# driver_1.net
KiCad netlist of a schematic drawn in EAGLE
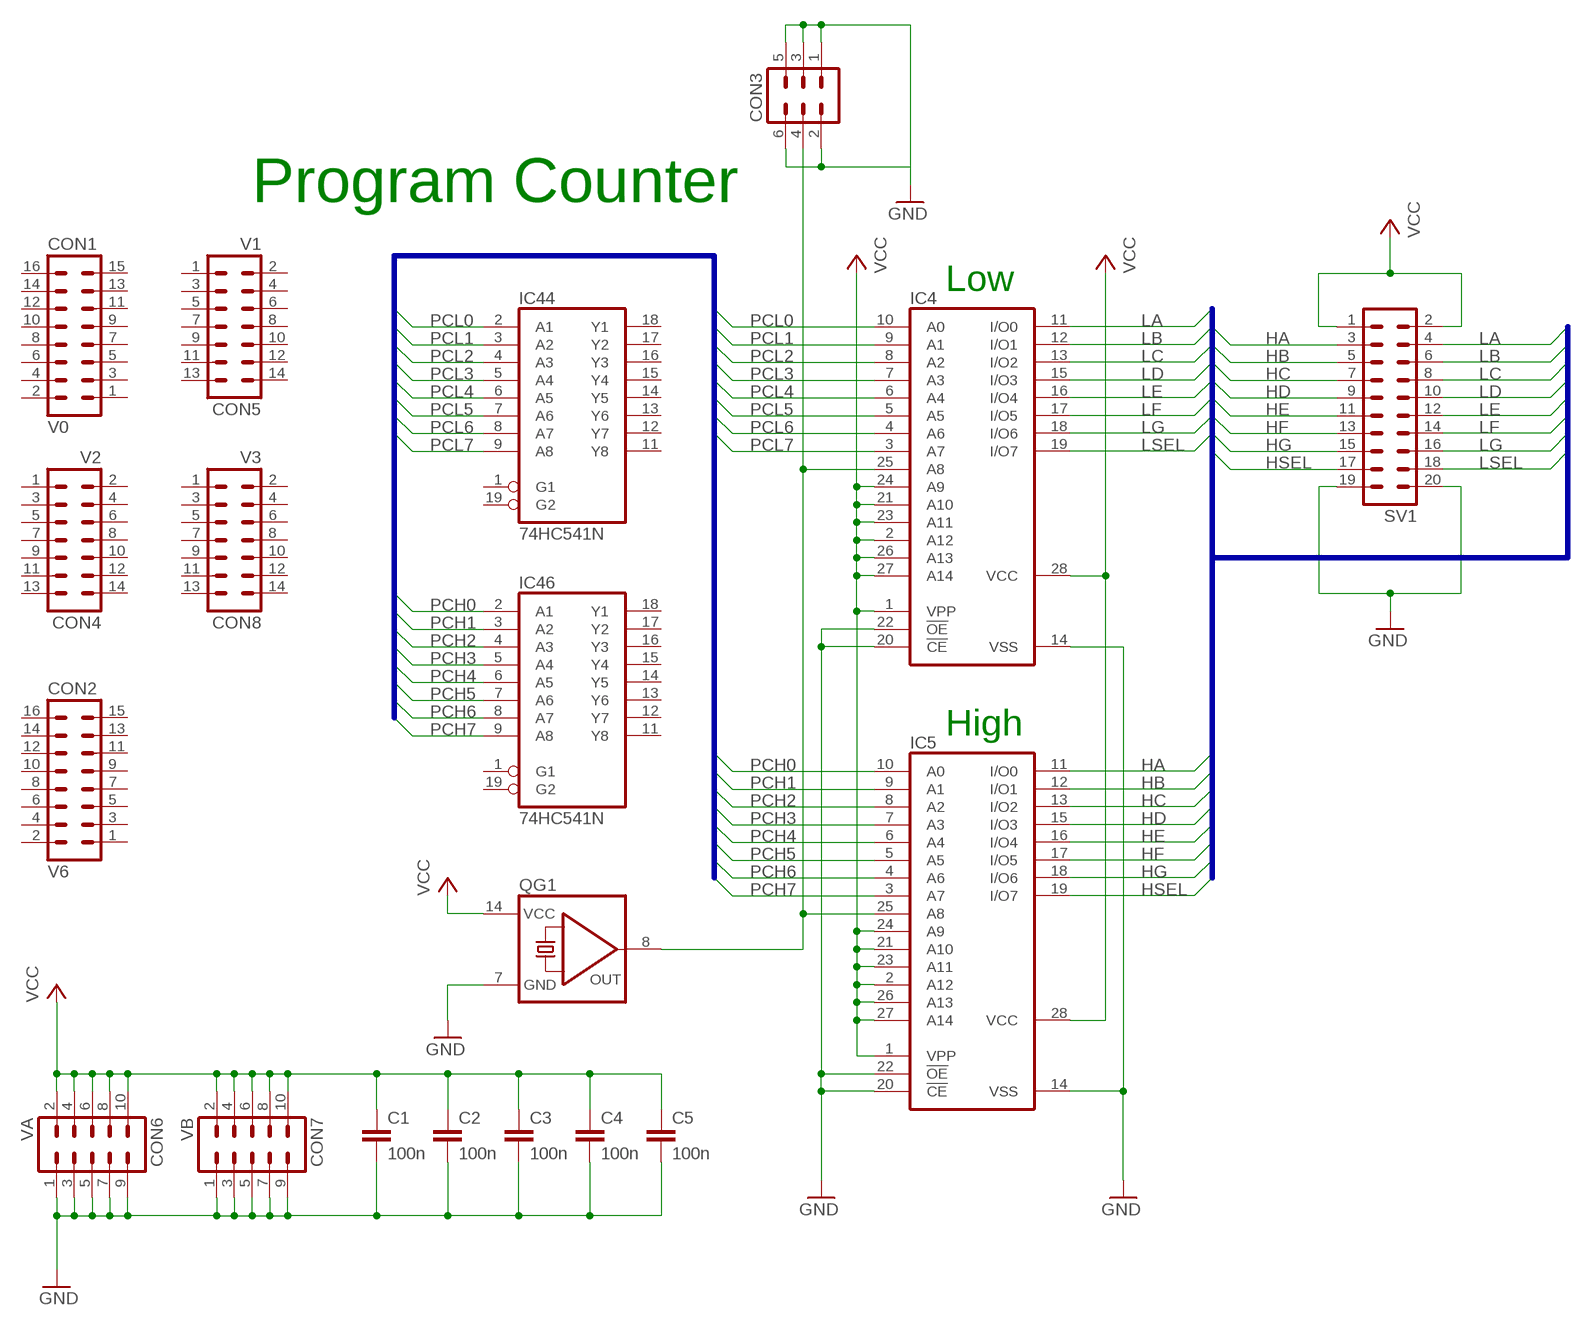
[diagram p0: schematic, sheet 1]

(export (version "E")
  (design (tool "Eeschema 10.0.6"))
  (components
    (comp (ref "C1")
      (value "100n")
      (footprint "eagle-import:C050-024X044")
      (libsource (lib "eagle-import") (part "C-EU050-024X044"))
    )
    (comp (ref "C2")
      (value "100n")
      (footprint "eagle-import:C050-024X044")
      (libsource (lib "eagle-import") (part "C-EU050-024X044"))
    )
    (comp (ref "C3")
      (value "100n")
      (footprint "eagle-import:C050-024X044")
      (libsource (lib "eagle-import") (part "C-EU050-024X044"))
    )
    (comp (ref "C4")
      (value "100n")
      (footprint "eagle-import:C050-024X044")
      (libsource (lib "eagle-import") (part "C-EU050-024X044"))
    )
    (comp (ref "C5")
      (value "100n")
      (footprint "eagle-import:C050-024X044")
      (libsource (lib "eagle-import") (part "C-EU050-024X044"))
    )
    (comp (ref "CON1")
      (value "V0")
      (footprint "eagle-import:ML16")
      (libsource (lib "eagle-import") (part "ML16"))
    )
    (comp (ref "CON2")
      (value "V6")
      (footprint "eagle-import:ML16")
      (libsource (lib "eagle-import") (part "ML16"))
    )
    (comp (ref "CON3")
      (value "ML6")
      (footprint "eagle-import:ML6")
      (libsource (lib "eagle-import") (part "ML6"))
    )
    (comp (ref "CON4")
      (value "V2")
      (footprint "eagle-import:ML14")
      (libsource (lib "eagle-import") (part "ML14"))
    )
    (comp (ref "CON5")
      (value "V1")
      (footprint "eagle-import:ML14")
      (fields (field (name "OC_FARNELL") "unknown") (field (name "OC_NEWARK") "unknown"))
      (libsource (lib "eagle-import") (part "ML14"))
    )
    (comp (ref "CON6")
      (value "VA")
      (footprint "eagle-import:ML10")
      (libsource (lib "eagle-import") (part "ML10"))
    )
    (comp (ref "CON7")
      (value "VB")
      (footprint "eagle-import:ML10")
      (libsource (lib "eagle-import") (part "ML10"))
    )
    (comp (ref "CON8")
      (value "V3")
      (footprint "eagle-import:ML14")
      (libsource (lib "eagle-import") (part "ML14"))
    )
    (comp (ref "IC4")
      (value "27C256AG")
      (footprint "eagle-import:DIL28-6")
      (libsource (lib "eagle-import") (part "27C256AG"))
    )
    (comp (ref "IC5")
      (value "27C256AG")
      (footprint "eagle-import:DIL28-6")
      (libsource (lib "eagle-import") (part "27C256AG"))
    )
    (comp (ref "IC44")
      (value "74HC541N")
      (footprint "eagle-import:DIL20")
      (libsource (lib "eagle-import") (part "74541NHC"))
    )
    (comp (ref "IC46")
      (value "74HC541N")
      (footprint "eagle-import:DIL20")
      (libsource (lib "eagle-import") (part "74541NHC"))
    )
    (comp (ref "QG1")
      (value "QG5860")
      (footprint "eagle-import:DIL14S")
      (libsource (lib "eagle-import") (part "QG5860"))
    )
    (comp (ref "SV1")
      (value "ML20L")
      (footprint "eagle-import:ML20L")
      (libsource (lib "eagle-import") (part "ML20L"))
    )
  )
  (nets
    (net (code "1") (name "/HA") (class "Default")
      (node (ref "IC5") (pin "11") (pinfunction "I/O0_11") (pintype "tri_state"))
      (node (ref "SV1") (pin "3") (pinfunction "3_3") (pintype "passive"))
    )
    (net (code "2") (name "/HB") (class "Default")
      (node (ref "IC5") (pin "12") (pinfunction "I/O1_12") (pintype "tri_state"))
      (node (ref "SV1") (pin "5") (pinfunction "5_5") (pintype "passive"))
    )
    (net (code "3") (name "/HC") (class "Default")
      (node (ref "IC5") (pin "13") (pinfunction "I/O2_13") (pintype "tri_state"))
      (node (ref "SV1") (pin "7") (pinfunction "7_7") (pintype "passive"))
    )
    (net (code "4") (name "/HD") (class "Default")
      (node (ref "IC5") (pin "15") (pinfunction "I/O3_15") (pintype "tri_state"))
      (node (ref "SV1") (pin "9") (pinfunction "9_9") (pintype "passive"))
    )
    (net (code "5") (name "/HE") (class "Default")
      (node (ref "IC5") (pin "16") (pinfunction "I/O4_16") (pintype "tri_state"))
      (node (ref "SV1") (pin "11") (pinfunction "11_11") (pintype "passive"))
    )
    (net (code "6") (name "/HF") (class "Default")
      (node (ref "IC5") (pin "17") (pinfunction "I/O5_17") (pintype "tri_state"))
      (node (ref "SV1") (pin "13") (pinfunction "13_13") (pintype "passive"))
    )
    (net (code "7") (name "/HG") (class "Default")
      (node (ref "IC5") (pin "18") (pinfunction "I/O6_18") (pintype "tri_state"))
      (node (ref "SV1") (pin "15") (pinfunction "15_15") (pintype "passive"))
    )
    (net (code "8") (name "/HSEL") (class "Default")
      (node (ref "IC5") (pin "19") (pinfunction "I/O7_19") (pintype "tri_state"))
      (node (ref "SV1") (pin "17") (pinfunction "17_17") (pintype "passive"))
    )
    (net (code "9") (name "/LA") (class "Default")
      (node (ref "IC4") (pin "11") (pinfunction "I/O0_11") (pintype "tri_state"))
      (node (ref "SV1") (pin "4") (pinfunction "4_4") (pintype "passive"))
    )
    (net (code "10") (name "/LB") (class "Default")
      (node (ref "IC4") (pin "12") (pinfunction "I/O1_12") (pintype "tri_state"))
      (node (ref "SV1") (pin "6") (pinfunction "6_6") (pintype "passive"))
    )
    (net (code "11") (name "/LC") (class "Default")
      (node (ref "IC4") (pin "13") (pinfunction "I/O2_13") (pintype "tri_state"))
      (node (ref "SV1") (pin "8") (pinfunction "8_8") (pintype "passive"))
    )
    (net (code "12") (name "/LD") (class "Default")
      (node (ref "IC4") (pin "15") (pinfunction "I/O3_15") (pintype "tri_state"))
      (node (ref "SV1") (pin "10") (pinfunction "10_10") (pintype "passive"))
    )
    (net (code "13") (name "/LE") (class "Default")
      (node (ref "IC4") (pin "16") (pinfunction "I/O4_16") (pintype "tri_state"))
      (node (ref "SV1") (pin "12") (pinfunction "12_12") (pintype "passive"))
    )
    (net (code "14") (name "/LF") (class "Default")
      (node (ref "IC4") (pin "17") (pinfunction "I/O5_17") (pintype "tri_state"))
      (node (ref "SV1") (pin "14") (pinfunction "14_14") (pintype "passive"))
    )
    (net (code "15") (name "/LG") (class "Default")
      (node (ref "IC4") (pin "18") (pinfunction "I/O6_18") (pintype "tri_state"))
      (node (ref "SV1") (pin "16") (pinfunction "16_16") (pintype "passive"))
    )
    (net (code "16") (name "/LSEL") (class "Default")
      (node (ref "IC4") (pin "19") (pinfunction "I/O7_19") (pintype "tri_state"))
      (node (ref "SV1") (pin "18") (pinfunction "18_18") (pintype "passive"))
    )
    (net (code "17") (name "/PCH0") (class "Default")
      (node (ref "IC46") (pin "2") (pinfunction "A1_2") (pintype "input"))
      (node (ref "IC5") (pin "10") (pinfunction "A0_10") (pintype "input"))
    )
    (net (code "18") (name "/PCH1") (class "Default")
      (node (ref "IC46") (pin "3") (pinfunction "A2_3") (pintype "input"))
      (node (ref "IC5") (pin "9") (pinfunction "A1_9") (pintype "input"))
    )
    (net (code "19") (name "/PCH2") (class "Default")
      (node (ref "IC46") (pin "4") (pinfunction "A3_4") (pintype "input"))
      (node (ref "IC5") (pin "8") (pinfunction "A2_8") (pintype "input"))
    )
    (net (code "20") (name "/PCH3") (class "Default")
      (node (ref "IC46") (pin "5") (pinfunction "A4_5") (pintype "input"))
      (node (ref "IC5") (pin "7") (pinfunction "A3_7") (pintype "input"))
    )
    (net (code "21") (name "/PCH4") (class "Default")
      (node (ref "IC46") (pin "6") (pinfunction "A5_6") (pintype "input"))
      (node (ref "IC5") (pin "6") (pinfunction "A4_6") (pintype "input"))
    )
    (net (code "22") (name "/PCH5") (class "Default")
      (node (ref "IC46") (pin "7") (pinfunction "A6_7") (pintype "input"))
      (node (ref "IC5") (pin "5") (pinfunction "A5_5") (pintype "input"))
    )
    (net (code "23") (name "/PCH6") (class "Default")
      (node (ref "IC46") (pin "8") (pinfunction "A7_8") (pintype "input"))
      (node (ref "IC5") (pin "4") (pinfunction "A6_4") (pintype "input"))
    )
    (net (code "24") (name "/PCH7") (class "Default")
      (node (ref "IC46") (pin "9") (pinfunction "A8_9") (pintype "input"))
      (node (ref "IC5") (pin "3") (pinfunction "A7_3") (pintype "input"))
    )
    (net (code "25") (name "/PCL0") (class "Default")
      (node (ref "IC4") (pin "10") (pinfunction "A0_10") (pintype "input"))
      (node (ref "IC44") (pin "2") (pinfunction "A1_2") (pintype "input"))
    )
    (net (code "26") (name "/PCL1") (class "Default")
      (node (ref "IC4") (pin "9") (pinfunction "A1_9") (pintype "input"))
      (node (ref "IC44") (pin "3") (pinfunction "A2_3") (pintype "input"))
    )
    (net (code "27") (name "/PCL2") (class "Default")
      (node (ref "IC4") (pin "8") (pinfunction "A2_8") (pintype "input"))
      (node (ref "IC44") (pin "4") (pinfunction "A3_4") (pintype "input"))
    )
    (net (code "28") (name "/PCL3") (class "Default")
      (node (ref "IC4") (pin "7") (pinfunction "A3_7") (pintype "input"))
      (node (ref "IC44") (pin "5") (pinfunction "A4_5") (pintype "input"))
    )
    (net (code "29") (name "/PCL4") (class "Default")
      (node (ref "IC4") (pin "6") (pinfunction "A4_6") (pintype "input"))
      (node (ref "IC44") (pin "6") (pinfunction "A5_6") (pintype "input"))
    )
    (net (code "30") (name "/PCL5") (class "Default")
      (node (ref "IC4") (pin "5") (pinfunction "A5_5") (pintype "input"))
      (node (ref "IC44") (pin "7") (pinfunction "A6_7") (pintype "input"))
    )
    (net (code "31") (name "/PCL6") (class "Default")
      (node (ref "IC4") (pin "4") (pinfunction "A6_4") (pintype "input"))
      (node (ref "IC44") (pin "8") (pinfunction "A7_8") (pintype "input"))
    )
    (net (code "32") (name "/PCL7") (class "Default")
      (node (ref "IC4") (pin "3") (pinfunction "A7_3") (pintype "input"))
      (node (ref "IC44") (pin "9") (pinfunction "A8_9") (pintype "input"))
    )
    (net (code "33") (name "GND") (class "Default")
      (node (ref "C1") (pin "2") (pinfunction "2_2") (pintype "passive"))
      (node (ref "C2") (pin "2") (pinfunction "2_2") (pintype "passive"))
      (node (ref "C3") (pin "2") (pinfunction "2_2") (pintype "passive"))
      (node (ref "C4") (pin "2") (pinfunction "2_2") (pintype "passive"))
      (node (ref "C5") (pin "2") (pinfunction "2_2") (pintype "passive"))
      (node (ref "CON3") (pin "1") (pinfunction "1_1") (pintype "passive"))
      (node (ref "CON3") (pin "2") (pinfunction "2_2") (pintype "passive"))
      (node (ref "CON3") (pin "3") (pinfunction "3_3") (pintype "passive"))
      (node (ref "CON3") (pin "5") (pinfunction "5_5") (pintype "passive"))
      (node (ref "CON3") (pin "6") (pinfunction "6_6") (pintype "passive"))
      (node (ref "CON6") (pin "1") (pinfunction "1_1") (pintype "passive"))
      (node (ref "CON6") (pin "3") (pinfunction "3_3") (pintype "passive"))
      (node (ref "CON6") (pin "5") (pinfunction "5_5") (pintype "passive"))
      (node (ref "CON6") (pin "7") (pinfunction "7_7") (pintype "passive"))
      (node (ref "CON6") (pin "9") (pinfunction "9_9") (pintype "passive"))
      (node (ref "CON7") (pin "1") (pinfunction "1_1") (pintype "passive"))
      (node (ref "CON7") (pin "3") (pinfunction "3_3") (pintype "passive"))
      (node (ref "CON7") (pin "5") (pinfunction "5_5") (pintype "passive"))
      (node (ref "CON7") (pin "7") (pinfunction "7_7") (pintype "passive"))
      (node (ref "CON7") (pin "9") (pinfunction "9_9") (pintype "passive"))
      (node (ref "IC4") (pin "14") (pinfunction "VSS_14") (pintype "power_in"))
      (node (ref "IC4") (pin "20") (pinfunction "~{CE}_20") (pintype "input"))
      (node (ref "IC4") (pin "22") (pinfunction "~{OE}_22") (pintype "input"))
      (node (ref "IC5") (pin "14") (pinfunction "VSS_14") (pintype "power_in"))
      (node (ref "IC5") (pin "20") (pinfunction "~{CE}_20") (pintype "input"))
      (node (ref "IC5") (pin "22") (pinfunction "~{OE}_22") (pintype "input"))
      (node (ref "QG1") (pin "7") (pinfunction "GND_7") (pintype "power_in"))
      (node (ref "SV1") (pin "19") (pinfunction "19_19") (pintype "passive"))
      (node (ref "SV1") (pin "20") (pinfunction "20_20") (pintype "passive"))
    )
    (net (code "34") (name "Net-(IC4-A8)") (class "Default")
      (node (ref "CON3") (pin "4") (pinfunction "4_4") (pintype "passive"))
      (node (ref "IC4") (pin "25") (pinfunction "A8_25") (pintype "input"))
      (node (ref "IC5") (pin "25") (pinfunction "A8_25") (pintype "input"))
      (node (ref "QG1") (pin "8") (pinfunction "OUT_8") (pintype "output"))
    )
    (net (code "35") (name "VCC") (class "Default")
      (node (ref "C1") (pin "1") (pinfunction "1_1") (pintype "passive"))
      (node (ref "C2") (pin "1") (pinfunction "1_1") (pintype "passive"))
      (node (ref "C3") (pin "1") (pinfunction "1_1") (pintype "passive"))
      (node (ref "C4") (pin "1") (pinfunction "1_1") (pintype "passive"))
      (node (ref "C5") (pin "1") (pinfunction "1_1") (pintype "passive"))
      (node (ref "CON6") (pin "10") (pinfunction "10_10") (pintype "passive"))
      (node (ref "CON6") (pin "2") (pinfunction "2_2") (pintype "passive"))
      (node (ref "CON6") (pin "4") (pinfunction "4_4") (pintype "passive"))
      (node (ref "CON6") (pin "6") (pinfunction "6_6") (pintype "passive"))
      (node (ref "CON6") (pin "8") (pinfunction "8_8") (pintype "passive"))
      (node (ref "CON7") (pin "10") (pinfunction "10_10") (pintype "passive"))
      (node (ref "CON7") (pin "2") (pinfunction "2_2") (pintype "passive"))
      (node (ref "CON7") (pin "4") (pinfunction "4_4") (pintype "passive"))
      (node (ref "CON7") (pin "6") (pinfunction "6_6") (pintype "passive"))
      (node (ref "CON7") (pin "8") (pinfunction "8_8") (pintype "passive"))
      (node (ref "IC4") (pin "1") (pinfunction "VPP_1") (pintype "input"))
      (node (ref "IC4") (pin "2") (pinfunction "A12_2") (pintype "input"))
      (node (ref "IC4") (pin "21") (pinfunction "A10_21") (pintype "input"))
      (node (ref "IC4") (pin "23") (pinfunction "A11_23") (pintype "input"))
      (node (ref "IC4") (pin "24") (pinfunction "A9_24") (pintype "input"))
      (node (ref "IC4") (pin "26") (pinfunction "A13_26") (pintype "input"))
      (node (ref "IC4") (pin "27") (pinfunction "A14_27") (pintype "input"))
      (node (ref "IC4") (pin "28") (pinfunction "VCC_28") (pintype "power_in"))
      (node (ref "IC5") (pin "1") (pinfunction "VPP_1") (pintype "input"))
      (node (ref "IC5") (pin "2") (pinfunction "A12_2") (pintype "input"))
      (node (ref "IC5") (pin "21") (pinfunction "A10_21") (pintype "input"))
      (node (ref "IC5") (pin "23") (pinfunction "A11_23") (pintype "input"))
      (node (ref "IC5") (pin "24") (pinfunction "A9_24") (pintype "input"))
      (node (ref "IC5") (pin "26") (pinfunction "A13_26") (pintype "input"))
      (node (ref "IC5") (pin "27") (pinfunction "A14_27") (pintype "input"))
      (node (ref "IC5") (pin "28") (pinfunction "VCC_28") (pintype "power_in"))
      (node (ref "QG1") (pin "14") (pinfunction "VCC_14") (pintype "power_in"))
      (node (ref "SV1") (pin "1") (pinfunction "1_1") (pintype "passive"))
      (node (ref "SV1") (pin "2") (pinfunction "2_2") (pintype "passive"))
    )
    (net (code "36") (name "unconnected-(CON1-Pad1)") (class "Default")
      (node (ref "CON1") (pin "1") (pinfunction "1_1") (pintype "passive"))
    )
    (net (code "37") (name "unconnected-(CON1-Pad2)") (class "Default")
      (node (ref "CON1") (pin "2") (pinfunction "2_2") (pintype "passive"))
    )
    (net (code "38") (name "unconnected-(CON1-Pad3)") (class "Default")
      (node (ref "CON1") (pin "3") (pinfunction "3_3") (pintype "passive"))
    )
    (net (code "39") (name "unconnected-(CON1-Pad4)") (class "Default")
      (node (ref "CON1") (pin "4") (pinfunction "4_4") (pintype "passive"))
    )
    (net (code "40") (name "unconnected-(CON1-Pad5)") (class "Default")
      (node (ref "CON1") (pin "5") (pinfunction "5_5") (pintype "passive"))
    )
    (net (code "41") (name "unconnected-(CON1-Pad6)") (class "Default")
      (node (ref "CON1") (pin "6") (pinfunction "6_6") (pintype "passive"))
    )
    (net (code "42") (name "unconnected-(CON1-Pad7)") (class "Default")
      (node (ref "CON1") (pin "7") (pinfunction "7_7") (pintype "passive"))
    )
    (net (code "43") (name "unconnected-(CON1-Pad8)") (class "Default")
      (node (ref "CON1") (pin "8") (pinfunction "8_8") (pintype "passive"))
    )
    (net (code "44") (name "unconnected-(CON1-Pad9)") (class "Default")
      (node (ref "CON1") (pin "9") (pinfunction "9_9") (pintype "passive"))
    )
    (net (code "45") (name "unconnected-(CON1-Pad10)") (class "Default")
      (node (ref "CON1") (pin "10") (pinfunction "10_10") (pintype "passive"))
    )
    (net (code "46") (name "unconnected-(CON1-Pad11)") (class "Default")
      (node (ref "CON1") (pin "11") (pinfunction "11_11") (pintype "passive"))
    )
    (net (code "47") (name "unconnected-(CON1-Pad12)") (class "Default")
      (node (ref "CON1") (pin "12") (pinfunction "12_12") (pintype "passive"))
    )
    (net (code "48") (name "unconnected-(CON1-Pad13)") (class "Default")
      (node (ref "CON1") (pin "13") (pinfunction "13_13") (pintype "passive"))
    )
    (net (code "49") (name "unconnected-(CON1-Pad14)") (class "Default")
      (node (ref "CON1") (pin "14") (pinfunction "14_14") (pintype "passive"))
    )
    (net (code "50") (name "unconnected-(CON1-Pad15)") (class "Default")
      (node (ref "CON1") (pin "15") (pinfunction "15_15") (pintype "passive"))
    )
    (net (code "51") (name "unconnected-(CON1-Pad16)") (class "Default")
      (node (ref "CON1") (pin "16") (pinfunction "16_16") (pintype "passive"))
    )
    (net (code "52") (name "unconnected-(CON2-Pad1)") (class "Default")
      (node (ref "CON2") (pin "1") (pinfunction "1_1") (pintype "passive"))
    )
    (net (code "53") (name "unconnected-(CON2-Pad2)") (class "Default")
      (node (ref "CON2") (pin "2") (pinfunction "2_2") (pintype "passive"))
    )
    (net (code "54") (name "unconnected-(CON2-Pad3)") (class "Default")
      (node (ref "CON2") (pin "3") (pinfunction "3_3") (pintype "passive"))
    )
    (net (code "55") (name "unconnected-(CON2-Pad4)") (class "Default")
      (node (ref "CON2") (pin "4") (pinfunction "4_4") (pintype "passive"))
    )
    (net (code "56") (name "unconnected-(CON2-Pad5)") (class "Default")
      (node (ref "CON2") (pin "5") (pinfunction "5_5") (pintype "passive"))
    )
    (net (code "57") (name "unconnected-(CON2-Pad6)") (class "Default")
      (node (ref "CON2") (pin "6") (pinfunction "6_6") (pintype "passive"))
    )
    (net (code "58") (name "unconnected-(CON2-Pad7)") (class "Default")
      (node (ref "CON2") (pin "7") (pinfunction "7_7") (pintype "passive"))
    )
    (net (code "59") (name "unconnected-(CON2-Pad8)") (class "Default")
      (node (ref "CON2") (pin "8") (pinfunction "8_8") (pintype "passive"))
    )
    (net (code "60") (name "unconnected-(CON2-Pad9)") (class "Default")
      (node (ref "CON2") (pin "9") (pinfunction "9_9") (pintype "passive"))
    )
    (net (code "61") (name "unconnected-(CON2-Pad10)") (class "Default")
      (node (ref "CON2") (pin "10") (pinfunction "10_10") (pintype "passive"))
    )
    (net (code "62") (name "unconnected-(CON2-Pad11)") (class "Default")
      (node (ref "CON2") (pin "11") (pinfunction "11_11") (pintype "passive"))
    )
    (net (code "63") (name "unconnected-(CON2-Pad12)") (class "Default")
      (node (ref "CON2") (pin "12") (pinfunction "12_12") (pintype "passive"))
    )
    (net (code "64") (name "unconnected-(CON2-Pad13)") (class "Default")
      (node (ref "CON2") (pin "13") (pinfunction "13_13") (pintype "passive"))
    )
    (net (code "65") (name "unconnected-(CON2-Pad14)") (class "Default")
      (node (ref "CON2") (pin "14") (pinfunction "14_14") (pintype "passive"))
    )
    (net (code "66") (name "unconnected-(CON2-Pad15)") (class "Default")
      (node (ref "CON2") (pin "15") (pinfunction "15_15") (pintype "passive"))
    )
    (net (code "67") (name "unconnected-(CON2-Pad16)") (class "Default")
      (node (ref "CON2") (pin "16") (pinfunction "16_16") (pintype "passive"))
    )
    (net (code "68") (name "unconnected-(CON4-Pad1)") (class "Default")
      (node (ref "CON4") (pin "1") (pinfunction "1_1") (pintype "passive"))
    )
    (net (code "69") (name "unconnected-(CON4-Pad2)") (class "Default")
      (node (ref "CON4") (pin "2") (pinfunction "2_2") (pintype "passive"))
    )
    (net (code "70") (name "unconnected-(CON4-Pad3)") (class "Default")
      (node (ref "CON4") (pin "3") (pinfunction "3_3") (pintype "passive"))
    )
    (net (code "71") (name "unconnected-(CON4-Pad4)") (class "Default")
      (node (ref "CON4") (pin "4") (pinfunction "4_4") (pintype "passive"))
    )
    (net (code "72") (name "unconnected-(CON4-Pad5)") (class "Default")
      (node (ref "CON4") (pin "5") (pinfunction "5_5") (pintype "passive"))
    )
    (net (code "73") (name "unconnected-(CON4-Pad6)") (class "Default")
      (node (ref "CON4") (pin "6") (pinfunction "6_6") (pintype "passive"))
    )
    (net (code "74") (name "unconnected-(CON4-Pad7)") (class "Default")
      (node (ref "CON4") (pin "7") (pinfunction "7_7") (pintype "passive"))
    )
    (net (code "75") (name "unconnected-(CON4-Pad8)") (class "Default")
      (node (ref "CON4") (pin "8") (pinfunction "8_8") (pintype "passive"))
    )
    (net (code "76") (name "unconnected-(CON4-Pad9)") (class "Default")
      (node (ref "CON4") (pin "9") (pinfunction "9_9") (pintype "passive"))
    )
    (net (code "77") (name "unconnected-(CON4-Pad10)") (class "Default")
      (node (ref "CON4") (pin "10") (pinfunction "10_10") (pintype "passive"))
    )
    (net (code "78") (name "unconnected-(CON4-Pad11)") (class "Default")
      (node (ref "CON4") (pin "11") (pinfunction "11_11") (pintype "passive"))
    )
    (net (code "79") (name "unconnected-(CON4-Pad12)") (class "Default")
      (node (ref "CON4") (pin "12") (pinfunction "12_12") (pintype "passive"))
    )
    (net (code "80") (name "unconnected-(CON4-Pad13)") (class "Default")
      (node (ref "CON4") (pin "13") (pinfunction "13_13") (pintype "passive"))
    )
    (net (code "81") (name "unconnected-(CON4-Pad14)") (class "Default")
      (node (ref "CON4") (pin "14") (pinfunction "14_14") (pintype "passive"))
    )
    (net (code "82") (name "unconnected-(CON5-Pad1)") (class "Default")
      (node (ref "CON5") (pin "1") (pinfunction "1_1") (pintype "passive"))
    )
    (net (code "83") (name "unconnected-(CON5-Pad2)") (class "Default")
      (node (ref "CON5") (pin "2") (pinfunction "2_2") (pintype "passive"))
    )
    (net (code "84") (name "unconnected-(CON5-Pad3)") (class "Default")
      (node (ref "CON5") (pin "3") (pinfunction "3_3") (pintype "passive"))
    )
    (net (code "85") (name "unconnected-(CON5-Pad4)") (class "Default")
      (node (ref "CON5") (pin "4") (pinfunction "4_4") (pintype "passive"))
    )
    (net (code "86") (name "unconnected-(CON5-Pad5)") (class "Default")
      (node (ref "CON5") (pin "5") (pinfunction "5_5") (pintype "passive"))
    )
    (net (code "87") (name "unconnected-(CON5-Pad6)") (class "Default")
      (node (ref "CON5") (pin "6") (pinfunction "6_6") (pintype "passive"))
    )
    (net (code "88") (name "unconnected-(CON5-Pad7)") (class "Default")
      (node (ref "CON5") (pin "7") (pinfunction "7_7") (pintype "passive"))
    )
    (net (code "89") (name "unconnected-(CON5-Pad8)") (class "Default")
      (node (ref "CON5") (pin "8") (pinfunction "8_8") (pintype "passive"))
    )
    (net (code "90") (name "unconnected-(CON5-Pad9)") (class "Default")
      (node (ref "CON5") (pin "9") (pinfunction "9_9") (pintype "passive"))
    )
    (net (code "91") (name "unconnected-(CON5-Pad10)") (class "Default")
      (node (ref "CON5") (pin "10") (pinfunction "10_10") (pintype "passive"))
    )
    (net (code "92") (name "unconnected-(CON5-Pad11)") (class "Default")
      (node (ref "CON5") (pin "11") (pinfunction "11_11") (pintype "passive"))
    )
    (net (code "93") (name "unconnected-(CON5-Pad12)") (class "Default")
      (node (ref "CON5") (pin "12") (pinfunction "12_12") (pintype "passive"))
    )
    (net (code "94") (name "unconnected-(CON5-Pad13)") (class "Default")
      (node (ref "CON5") (pin "13") (pinfunction "13_13") (pintype "passive"))
    )
    (net (code "95") (name "unconnected-(CON5-Pad14)") (class "Default")
      (node (ref "CON5") (pin "14") (pinfunction "14_14") (pintype "passive"))
    )
    (net (code "96") (name "unconnected-(CON8-Pad1)") (class "Default")
      (node (ref "CON8") (pin "1") (pinfunction "1_1") (pintype "passive"))
    )
    (net (code "97") (name "unconnected-(CON8-Pad2)") (class "Default")
      (node (ref "CON8") (pin "2") (pinfunction "2_2") (pintype "passive"))
    )
    (net (code "98") (name "unconnected-(CON8-Pad3)") (class "Default")
      (node (ref "CON8") (pin "3") (pinfunction "3_3") (pintype "passive"))
    )
    (net (code "99") (name "unconnected-(CON8-Pad4)") (class "Default")
      (node (ref "CON8") (pin "4") (pinfunction "4_4") (pintype "passive"))
    )
    (net (code "100") (name "unconnected-(CON8-Pad5)") (class "Default")
      (node (ref "CON8") (pin "5") (pinfunction "5_5") (pintype "passive"))
    )
    (net (code "101") (name "unconnected-(CON8-Pad6)") (class "Default")
      (node (ref "CON8") (pin "6") (pinfunction "6_6") (pintype "passive"))
    )
    (net (code "102") (name "unconnected-(CON8-Pad7)") (class "Default")
      (node (ref "CON8") (pin "7") (pinfunction "7_7") (pintype "passive"))
    )
    (net (code "103") (name "unconnected-(CON8-Pad8)") (class "Default")
      (node (ref "CON8") (pin "8") (pinfunction "8_8") (pintype "passive"))
    )
    (net (code "104") (name "unconnected-(CON8-Pad9)") (class "Default")
      (node (ref "CON8") (pin "9") (pinfunction "9_9") (pintype "passive"))
    )
    (net (code "105") (name "unconnected-(CON8-Pad10)") (class "Default")
      (node (ref "CON8") (pin "10") (pinfunction "10_10") (pintype "passive"))
    )
    (net (code "106") (name "unconnected-(CON8-Pad11)") (class "Default")
      (node (ref "CON8") (pin "11") (pinfunction "11_11") (pintype "passive"))
    )
    (net (code "107") (name "unconnected-(CON8-Pad12)") (class "Default")
      (node (ref "CON8") (pin "12") (pinfunction "12_12") (pintype "passive"))
    )
    (net (code "108") (name "unconnected-(CON8-Pad13)") (class "Default")
      (node (ref "CON8") (pin "13") (pinfunction "13_13") (pintype "passive"))
    )
    (net (code "109") (name "unconnected-(CON8-Pad14)") (class "Default")
      (node (ref "CON8") (pin "14") (pinfunction "14_14") (pintype "passive"))
    )
    (net (code "110") (name "unconnected-(IC44A-G1-Pad1)") (class "Default")
      (node (ref "IC44") (pin "1") (pinfunction "G1_1") (pintype "input"))
    )
    (net (code "111") (name "unconnected-(IC44A-G2-Pad19)") (class "Default")
      (node (ref "IC44") (pin "19") (pinfunction "G2_19") (pintype "input"))
    )
    (net (code "112") (name "unconnected-(IC44A-Y1-Pad18)") (class "Default")
      (node (ref "IC44") (pin "18") (pinfunction "Y1_18") (pintype "tri_state"))
    )
    (net (code "113") (name "unconnected-(IC44A-Y2-Pad17)") (class "Default")
      (node (ref "IC44") (pin "17") (pinfunction "Y2_17") (pintype "tri_state"))
    )
    (net (code "114") (name "unconnected-(IC44A-Y3-Pad16)") (class "Default")
      (node (ref "IC44") (pin "16") (pinfunction "Y3_16") (pintype "tri_state"))
    )
    (net (code "115") (name "unconnected-(IC44A-Y4-Pad15)") (class "Default")
      (node (ref "IC44") (pin "15") (pinfunction "Y4_15") (pintype "tri_state"))
    )
    (net (code "116") (name "unconnected-(IC44A-Y5-Pad14)") (class "Default")
      (node (ref "IC44") (pin "14") (pinfunction "Y5_14") (pintype "tri_state"))
    )
    (net (code "117") (name "unconnected-(IC44A-Y6-Pad13)") (class "Default")
      (node (ref "IC44") (pin "13") (pinfunction "Y6_13") (pintype "tri_state"))
    )
    (net (code "118") (name "unconnected-(IC44A-Y7-Pad12)") (class "Default")
      (node (ref "IC44") (pin "12") (pinfunction "Y7_12") (pintype "tri_state"))
    )
    (net (code "119") (name "unconnected-(IC44A-Y8-Pad11)") (class "Default")
      (node (ref "IC44") (pin "11") (pinfunction "Y8_11") (pintype "tri_state"))
    )
    (net (code "120") (name "unconnected-(IC46A-G1-Pad1)") (class "Default")
      (node (ref "IC46") (pin "1") (pinfunction "G1_1") (pintype "input"))
    )
    (net (code "121") (name "unconnected-(IC46A-G2-Pad19)") (class "Default")
      (node (ref "IC46") (pin "19") (pinfunction "G2_19") (pintype "input"))
    )
    (net (code "122") (name "unconnected-(IC46A-Y1-Pad18)") (class "Default")
      (node (ref "IC46") (pin "18") (pinfunction "Y1_18") (pintype "tri_state"))
    )
    (net (code "123") (name "unconnected-(IC46A-Y2-Pad17)") (class "Default")
      (node (ref "IC46") (pin "17") (pinfunction "Y2_17") (pintype "tri_state"))
    )
    (net (code "124") (name "unconnected-(IC46A-Y3-Pad16)") (class "Default")
      (node (ref "IC46") (pin "16") (pinfunction "Y3_16") (pintype "tri_state"))
    )
    (net (code "125") (name "unconnected-(IC46A-Y4-Pad15)") (class "Default")
      (node (ref "IC46") (pin "15") (pinfunction "Y4_15") (pintype "tri_state"))
    )
    (net (code "126") (name "unconnected-(IC46A-Y5-Pad14)") (class "Default")
      (node (ref "IC46") (pin "14") (pinfunction "Y5_14") (pintype "tri_state"))
    )
    (net (code "127") (name "unconnected-(IC46A-Y6-Pad13)") (class "Default")
      (node (ref "IC46") (pin "13") (pinfunction "Y6_13") (pintype "tri_state"))
    )
    (net (code "128") (name "unconnected-(IC46A-Y7-Pad12)") (class "Default")
      (node (ref "IC46") (pin "12") (pinfunction "Y7_12") (pintype "tri_state"))
    )
    (net (code "129") (name "unconnected-(IC46A-Y8-Pad11)") (class "Default")
      (node (ref "IC46") (pin "11") (pinfunction "Y8_11") (pintype "tri_state"))
    )
  )
)
